# fhd-gs.net
KiCad netlist of a schematic drawn in EAGLE
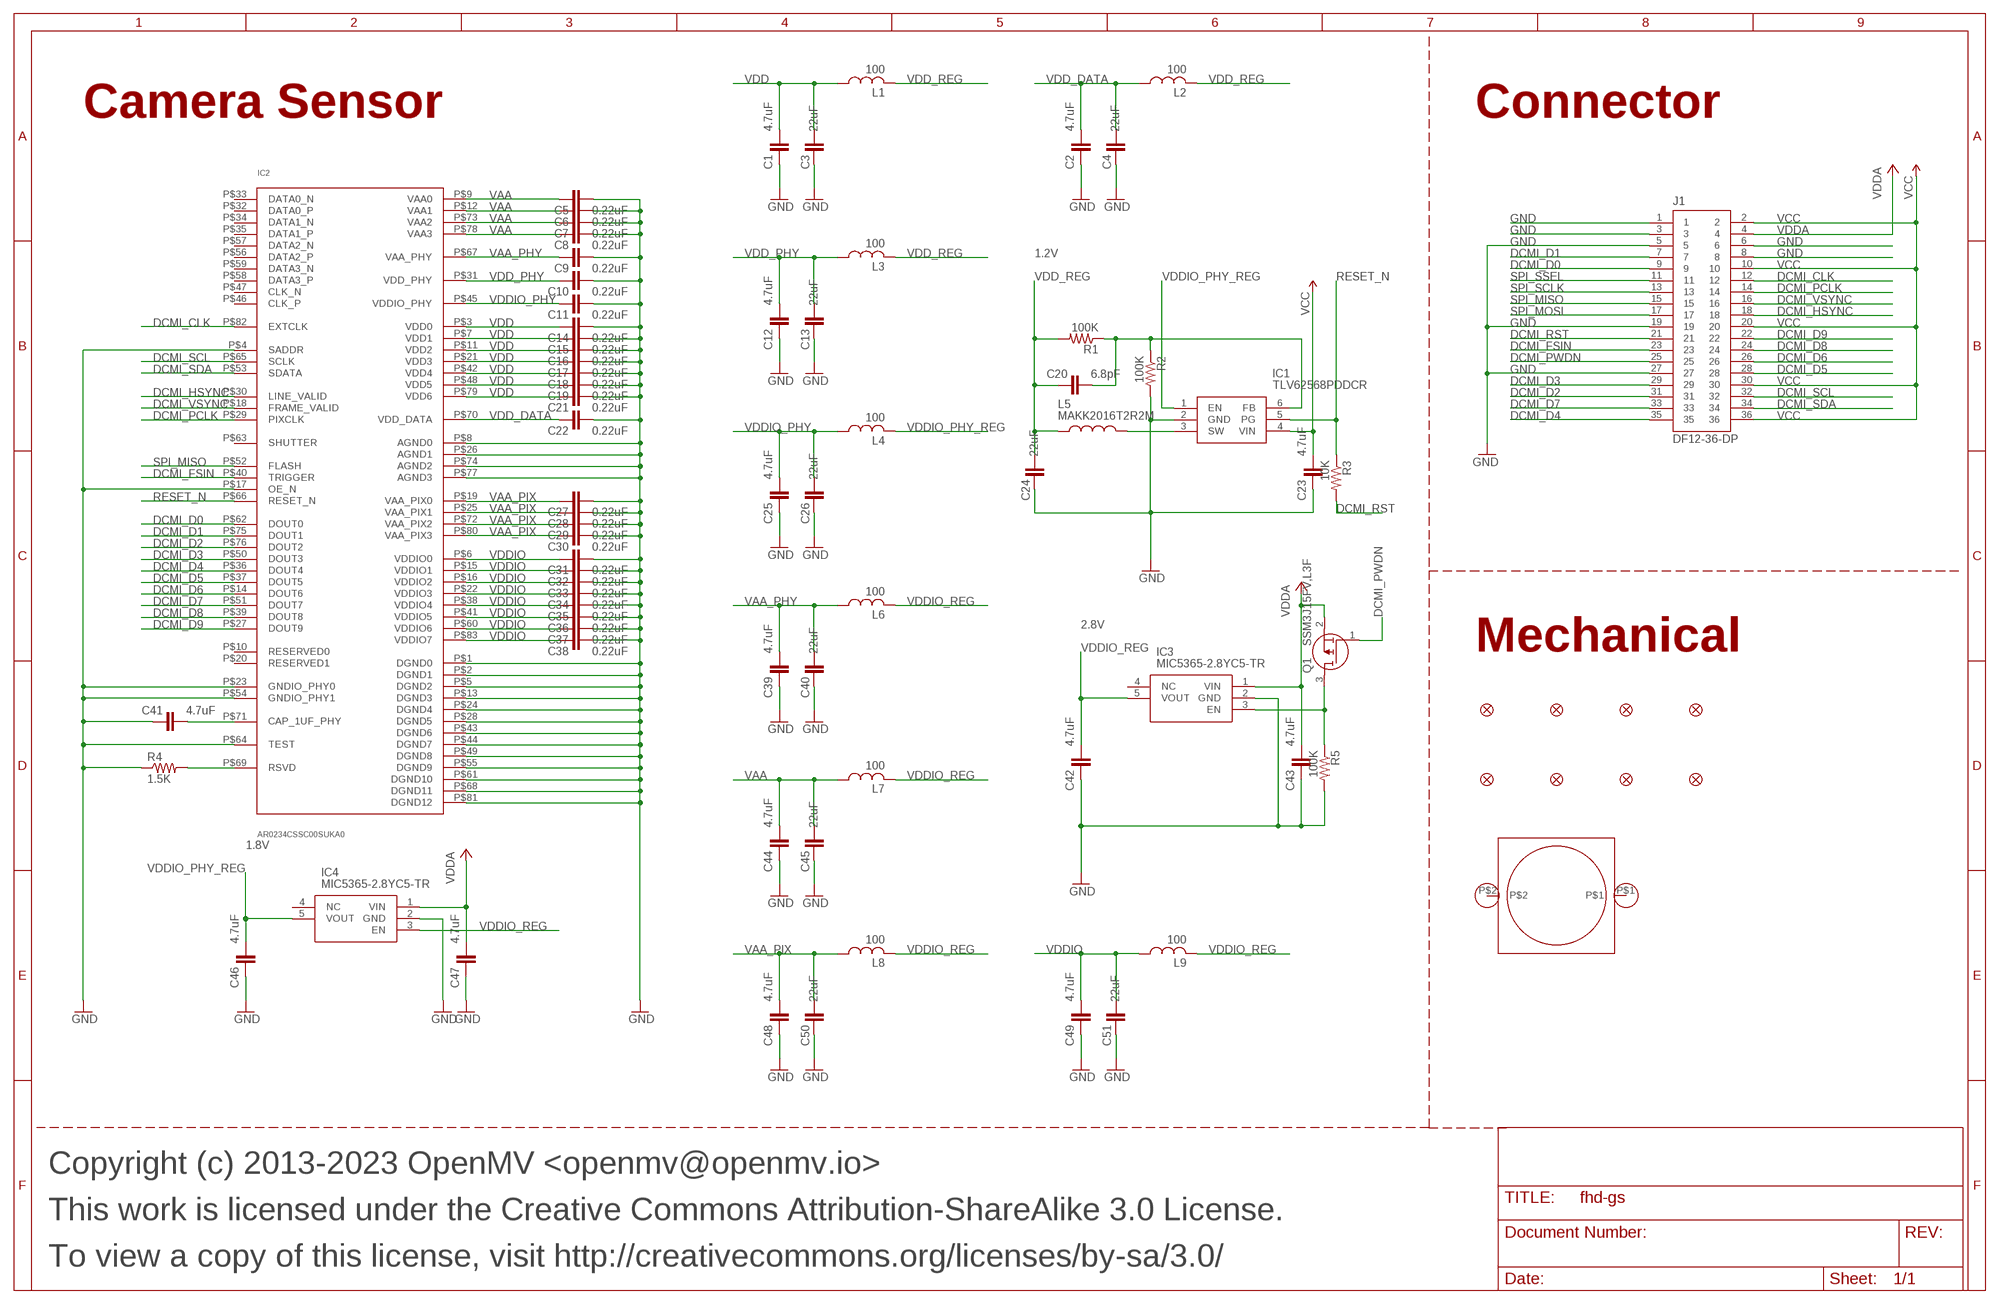
[diagram p0: schematic, sheet 1]

(export (version "E")
  (design (tool "Eeschema 10.0.6"))
  (components
    (comp (ref "C1")
      (value "4.7uF")
      (footprint "eagle-import:0402")
      (fields (field (name "MPN") "JMK105BBJ475MV-F"))
      (libsource (lib "eagle-import") (part "CAP_0402"))
    )
    (comp (ref "C2")
      (value "4.7uF")
      (footprint "eagle-import:0402")
      (fields (field (name "MPN") "JMK105BBJ475MV-F"))
      (libsource (lib "eagle-import") (part "CAP_0402"))
    )
    (comp (ref "C3")
      (value "22uF")
      (footprint "eagle-import:0805")
      (fields (field (name "MPN") "CL21A226MQQNNNE"))
      (libsource (lib "eagle-import") (part "22UF-0805-6.3V-20%"))
    )
    (comp (ref "C4")
      (value "22uF")
      (footprint "eagle-import:0805")
      (fields (field (name "MPN") "CL21A226MQQNNNE"))
      (libsource (lib "eagle-import") (part "22UF-0805-6.3V-20%"))
    )
    (comp (ref "C5")
      (value "0.22uF")
      (footprint "eagle-import:C0201")
      (fields (field (name "MPN") "GRM033R60J224ME15D"))
      (libsource (lib "eagle-import") (part "C-EUC0201"))
    )
    (comp (ref "C6")
      (value "0.22uF")
      (footprint "eagle-import:C0201")
      (fields (field (name "MPN") "GRM033R60J224ME15D"))
      (libsource (lib "eagle-import") (part "C-EUC0201"))
    )
    (comp (ref "C7")
      (value "0.22uF")
      (footprint "eagle-import:C0201")
      (fields (field (name "MPN") "GRM033R60J224ME15D"))
      (libsource (lib "eagle-import") (part "C-EUC0201"))
    )
    (comp (ref "C8")
      (value "0.22uF")
      (footprint "eagle-import:C0201")
      (fields (field (name "MPN") "GRM033R60J224ME15D"))
      (libsource (lib "eagle-import") (part "C-EUC0201"))
    )
    (comp (ref "C9")
      (value "0.22uF")
      (footprint "eagle-import:C0201")
      (fields (field (name "MPN") "GRM033R60J224ME15D"))
      (libsource (lib "eagle-import") (part "C-EUC0201"))
    )
    (comp (ref "C10")
      (value "0.22uF")
      (footprint "eagle-import:C0201")
      (fields (field (name "MPN") "GRM033R60J224ME15D"))
      (libsource (lib "eagle-import") (part "C-EUC0201"))
    )
    (comp (ref "C11")
      (value "0.22uF")
      (footprint "eagle-import:C0201")
      (fields (field (name "MPN") "GRM033R60J224ME15D"))
      (libsource (lib "eagle-import") (part "C-EUC0201"))
    )
    (comp (ref "C12")
      (value "4.7uF")
      (footprint "eagle-import:0402")
      (fields (field (name "MPN") "JMK105BBJ475MV-F"))
      (libsource (lib "eagle-import") (part "CAP_0402"))
    )
    (comp (ref "C13")
      (value "22uF")
      (footprint "eagle-import:0805")
      (fields (field (name "MPN") "CL21A226MQQNNNE"))
      (libsource (lib "eagle-import") (part "22UF-0805-6.3V-20%"))
    )
    (comp (ref "C14")
      (value "0.22uF")
      (footprint "eagle-import:C0201")
      (fields (field (name "MPN") "GRM033R60J224ME15D"))
      (libsource (lib "eagle-import") (part "C-EUC0201"))
    )
    (comp (ref "C15")
      (value "0.22uF")
      (footprint "eagle-import:C0201")
      (fields (field (name "MPN") "GRM033R60J224ME15D"))
      (libsource (lib "eagle-import") (part "C-EUC0201"))
    )
    (comp (ref "C16")
      (value "0.22uF")
      (footprint "eagle-import:C0201")
      (fields (field (name "MPN") "GRM033R60J224ME15D"))
      (libsource (lib "eagle-import") (part "C-EUC0201"))
    )
    (comp (ref "C17")
      (value "0.22uF")
      (footprint "eagle-import:C0201")
      (fields (field (name "MPN") "GRM033R60J224ME15D"))
      (libsource (lib "eagle-import") (part "C-EUC0201"))
    )
    (comp (ref "C18")
      (value "0.22uF")
      (footprint "eagle-import:C0201")
      (fields (field (name "MPN") "GRM033R60J224ME15D"))
      (libsource (lib "eagle-import") (part "C-EUC0201"))
    )
    (comp (ref "C19")
      (value "0.22uF")
      (footprint "eagle-import:C0201")
      (fields (field (name "MPN") "GRM033R60J224ME15D"))
      (libsource (lib "eagle-import") (part "C-EUC0201"))
    )
    (comp (ref "C20")
      (value "6.8pF")
      (footprint "eagle-import:0402")
      (fields (field (name "MPN") "GRM1555C1H6R8DA01D"))
      (libsource (lib "eagle-import") (part "CAP_0402"))
    )
    (comp (ref "C21")
      (value "0.22uF")
      (footprint "eagle-import:C0201")
      (fields (field (name "MPN") "GRM033R60J224ME15D"))
      (libsource (lib "eagle-import") (part "C-EUC0201"))
    )
    (comp (ref "C22")
      (value "0.22uF")
      (footprint "eagle-import:C0201")
      (fields (field (name "MPN") "GRM033R60J224ME15D"))
      (libsource (lib "eagle-import") (part "C-EUC0201"))
    )
    (comp (ref "C23")
      (value "4.7uF")
      (footprint "eagle-import:0402")
      (fields (field (name "MPN") "JMK105BBJ475MV-F"))
      (libsource (lib "eagle-import") (part "CAP_0402"))
    )
    (comp (ref "C24")
      (value "22uF")
      (footprint "eagle-import:0805")
      (fields (field (name "MPN") "CL21A226MQQNNNE"))
      (libsource (lib "eagle-import") (part "22UF-0805-6.3V-20%"))
    )
    (comp (ref "C25")
      (value "4.7uF")
      (footprint "eagle-import:0402")
      (fields (field (name "MPN") "JMK105BBJ475MV-F"))
      (libsource (lib "eagle-import") (part "CAP_0402"))
    )
    (comp (ref "C26")
      (value "22uF")
      (footprint "eagle-import:0805")
      (fields (field (name "MPN") "CL21A226MQQNNNE"))
      (libsource (lib "eagle-import") (part "22UF-0805-6.3V-20%"))
    )
    (comp (ref "C27")
      (value "0.22uF")
      (footprint "eagle-import:C0201")
      (fields (field (name "MPN") "GRM033R60J224ME15D"))
      (libsource (lib "eagle-import") (part "C-EUC0201"))
    )
    (comp (ref "C28")
      (value "0.22uF")
      (footprint "eagle-import:C0201")
      (fields (field (name "MPN") "GRM033R60J224ME15D"))
      (libsource (lib "eagle-import") (part "C-EUC0201"))
    )
    (comp (ref "C29")
      (value "0.22uF")
      (footprint "eagle-import:C0201")
      (fields (field (name "MPN") "GRM033R60J224ME15D"))
      (libsource (lib "eagle-import") (part "C-EUC0201"))
    )
    (comp (ref "C30")
      (value "0.22uF")
      (footprint "eagle-import:C0201")
      (fields (field (name "MPN") "GRM033R60J224ME15D"))
      (libsource (lib "eagle-import") (part "C-EUC0201"))
    )
    (comp (ref "C31")
      (value "0.22uF")
      (footprint "eagle-import:C0201")
      (fields (field (name "MPN") "GRM033R60J224ME15D"))
      (libsource (lib "eagle-import") (part "C-EUC0201"))
    )
    (comp (ref "C32")
      (value "0.22uF")
      (footprint "eagle-import:C0201")
      (fields (field (name "MPN") "GRM033R60J224ME15D"))
      (libsource (lib "eagle-import") (part "C-EUC0201"))
    )
    (comp (ref "C33")
      (value "0.22uF")
      (footprint "eagle-import:C0201")
      (fields (field (name "MPN") "GRM033R60J224ME15D"))
      (libsource (lib "eagle-import") (part "C-EUC0201"))
    )
    (comp (ref "C34")
      (value "0.22uF")
      (footprint "eagle-import:C0201")
      (fields (field (name "MPN") "GRM033R60J224ME15D"))
      (libsource (lib "eagle-import") (part "C-EUC0201"))
    )
    (comp (ref "C35")
      (value "0.22uF")
      (footprint "eagle-import:C0201")
      (fields (field (name "MPN") "GRM033R60J224ME15D"))
      (libsource (lib "eagle-import") (part "C-EUC0201"))
    )
    (comp (ref "C36")
      (value "0.22uF")
      (footprint "eagle-import:C0201")
      (fields (field (name "MPN") "GRM033R60J224ME15D"))
      (libsource (lib "eagle-import") (part "C-EUC0201"))
    )
    (comp (ref "C37")
      (value "0.22uF")
      (footprint "eagle-import:C0201")
      (fields (field (name "MPN") "GRM033R60J224ME15D"))
      (libsource (lib "eagle-import") (part "C-EUC0201"))
    )
    (comp (ref "C38")
      (value "0.22uF")
      (footprint "eagle-import:C0201")
      (fields (field (name "MPN") "GRM033R60J224ME15D"))
      (libsource (lib "eagle-import") (part "C-EUC0201"))
    )
    (comp (ref "C39")
      (value "4.7uF")
      (footprint "eagle-import:0402")
      (fields (field (name "MPN") "JMK105BBJ475MV-F"))
      (libsource (lib "eagle-import") (part "CAP_0402"))
    )
    (comp (ref "C40")
      (value "22uF")
      (footprint "eagle-import:0805")
      (fields (field (name "MPN") "CL21A226MQQNNNE"))
      (libsource (lib "eagle-import") (part "22UF-0805-6.3V-20%"))
    )
    (comp (ref "C41")
      (value "4.7uF")
      (footprint "eagle-import:0402")
      (fields (field (name "MPN") "JMK105BBJ475MV-F"))
      (libsource (lib "eagle-import") (part "CAP_0402"))
    )
    (comp (ref "C42")
      (value "4.7uF")
      (footprint "eagle-import:0402")
      (fields (field (name "MPN") "JMK105BBJ475MV-F"))
      (libsource (lib "eagle-import") (part "CAP_0402"))
    )
    (comp (ref "C43")
      (value "4.7uF")
      (footprint "eagle-import:0402")
      (fields (field (name "MPN") "JMK105BBJ475MV-F"))
      (libsource (lib "eagle-import") (part "CAP_0402"))
    )
    (comp (ref "C44")
      (value "4.7uF")
      (footprint "eagle-import:0402")
      (fields (field (name "MPN") "JMK105BBJ475MV-F"))
      (libsource (lib "eagle-import") (part "CAP_0402"))
    )
    (comp (ref "C45")
      (value "22uF")
      (footprint "eagle-import:0805")
      (fields (field (name "MPN") "CL21A226MQQNNNE"))
      (libsource (lib "eagle-import") (part "22UF-0805-6.3V-20%"))
    )
    (comp (ref "C46")
      (value "4.7uF")
      (footprint "eagle-import:0402")
      (fields (field (name "MPN") "JMK105BBJ475MV-F"))
      (libsource (lib "eagle-import") (part "CAP_0402"))
    )
    (comp (ref "C47")
      (value "4.7uF")
      (footprint "eagle-import:0402")
      (fields (field (name "MPN") "JMK105BBJ475MV-F"))
      (libsource (lib "eagle-import") (part "CAP_0402"))
    )
    (comp (ref "C48")
      (value "4.7uF")
      (footprint "eagle-import:0402")
      (fields (field (name "MPN") "JMK105BBJ475MV-F"))
      (libsource (lib "eagle-import") (part "CAP_0402"))
    )
    (comp (ref "C49")
      (value "4.7uF")
      (footprint "eagle-import:0402")
      (fields (field (name "MPN") "JMK105BBJ475MV-F"))
      (libsource (lib "eagle-import") (part "CAP_0402"))
    )
    (comp (ref "C50")
      (value "22uF")
      (footprint "eagle-import:0805")
      (fields (field (name "MPN") "CL21A226MQQNNNE"))
      (libsource (lib "eagle-import") (part "22UF-0805-6.3V-20%"))
    )
    (comp (ref "C51")
      (value "22uF")
      (footprint "eagle-import:0805")
      (fields (field (name "MPN") "CL21A226MQQNNNE"))
      (libsource (lib "eagle-import") (part "22UF-0805-6.3V-20%"))
    )
    (comp (ref "FD1")
      (value "FIDUCIAL1X2")
      (footprint "eagle-import:FIDUCIAL-1X2")
      (libsource (lib "eagle-import") (part "FIDUCIAL1X2"))
    )
    (comp (ref "FD2")
      (value "FIDUCIAL1X2")
      (footprint "eagle-import:FIDUCIAL-1X2")
      (libsource (lib "eagle-import") (part "FIDUCIAL1X2"))
    )
    (comp (ref "FD3")
      (value "FIDUCIAL1X2")
      (footprint "eagle-import:FIDUCIAL-1X2")
      (libsource (lib "eagle-import") (part "FIDUCIAL1X2"))
    )
    (comp (ref "FD4")
      (value "FIDUCIAL1X2")
      (footprint "eagle-import:FIDUCIAL-1X2")
      (libsource (lib "eagle-import") (part "FIDUCIAL1X2"))
    )
    (comp (ref "FD5")
      (value "FIDUCIAL1X2")
      (footprint "eagle-import:FIDUCIAL-1X2")
      (libsource (lib "eagle-import") (part "FIDUCIAL1X2"))
    )
    (comp (ref "FD6")
      (value "FIDUCIAL1X2")
      (footprint "eagle-import:FIDUCIAL-1X2")
      (libsource (lib "eagle-import") (part "FIDUCIAL1X2"))
    )
    (comp (ref "FD7")
      (value "FIDUCIAL1X2")
      (footprint "eagle-import:FIDUCIAL-1X2")
      (libsource (lib "eagle-import") (part "FIDUCIAL1X2"))
    )
    (comp (ref "FD8")
      (value "FIDUCIAL1X2")
      (footprint "eagle-import:FIDUCIAL-1X2")
      (libsource (lib "eagle-import") (part "FIDUCIAL1X2"))
    )
    (comp (ref "H1")
      (value "LENSMOUNT20MM")
      (footprint "eagle-import:LENSMOUNT-20MM")
      (libsource (lib "eagle-import") (part "LENSMOUNT20MM"))
    )
    (comp (ref "IC1")
      (value "TLV62568PDDCR")
      (footprint "eagle-import:SOT95P280X110-6N")
      (fields (field (name "MOUSER_PART_NUMBER") "595-TLV62568PDDCR"))
      (libsource (lib "eagle-import") (part "TLV62568PDDCR"))
    )
    (comp (ref "IC2")
      (value "AR0234CSSC00SUKA0")
      (footprint "eagle-import:AR0234CSSC00SUKA0")
      (libsource (lib "eagle-import") (part "AR0234CSSC00SUKA0"))
    )
    (comp (ref "IC3")
      (value "MIC5365-2.8YC5-TR")
      (footprint "eagle-import:SOT65P210X110-5N")
      (fields (field (name "MOUSER_PART_NUMBER") "998-MIC5365-2.8YC5TR"))
      (libsource (lib "eagle-import") (part "MIC5365-2.8YC5-TR"))
    )
    (comp (ref "IC4")
      (value "MIC5365-2.8YC5-TR")
      (footprint "eagle-import:SOT65P210X110-5N")
      (fields (field (name "MOUSER_PART_NUMBER") "998-MIC5365-2.8YC5TR"))
      (libsource (lib "eagle-import") (part "MIC5365-2.8YC5-TR"))
    )
    (comp (ref "J1")
      (value "DF12-36-DP")
      (footprint "eagle-import:DF12-36-DP")
      (fields (field (name "MPN") "DF12NB(3.0)-36DP-0.5V(51)"))
      (libsource (lib "eagle-import") (part "DF12-36-DP"))
    )
    (comp (ref "L1")
      (value "100")
      (footprint "eagle-import:0402")
      (fields (field (name "MPN") "MFBM1V1005-101-R"))
      (libsource (lib "eagle-import") (part "INDUCTOR_0402"))
    )
    (comp (ref "L2")
      (value "100")
      (footprint "eagle-import:0402")
      (fields (field (name "MPN") "MFBM1V1005-101-R"))
      (libsource (lib "eagle-import") (part "INDUCTOR_0402"))
    )
    (comp (ref "L3")
      (value "100")
      (footprint "eagle-import:0402")
      (fields (field (name "MPN") "MFBM1V1005-101-R"))
      (libsource (lib "eagle-import") (part "INDUCTOR_0402"))
    )
    (comp (ref "L4")
      (value "100")
      (footprint "eagle-import:0402")
      (fields (field (name "MPN") "MFBM1V1005-101-R"))
      (libsource (lib "eagle-import") (part "INDUCTOR_0402"))
    )
    (comp (ref "L5")
      (value "MAKK2016T2R2M")
      (footprint "eagle-import:INDC2016X100N")
      (fields (field (name "MF") "Taiyo Yuden"))
      (libsource (lib "eagle-import") (part "MAKK2016T2R2M"))
    )
    (comp (ref "L6")
      (value "100")
      (footprint "eagle-import:0402")
      (fields (field (name "MPN") "MFBM1V1005-101-R"))
      (libsource (lib "eagle-import") (part "INDUCTOR_0402"))
    )
    (comp (ref "L7")
      (value "100")
      (footprint "eagle-import:0402")
      (fields (field (name "MPN") "MFBM1V1005-101-R"))
      (libsource (lib "eagle-import") (part "INDUCTOR_0402"))
    )
    (comp (ref "L8")
      (value "100")
      (footprint "eagle-import:0402")
      (fields (field (name "MPN") "MFBM1V1005-101-R"))
      (libsource (lib "eagle-import") (part "INDUCTOR_0402"))
    )
    (comp (ref "L9")
      (value "100")
      (footprint "eagle-import:0402")
      (fields (field (name "MPN") "MFBM1V1005-101-R"))
      (libsource (lib "eagle-import") (part "INDUCTOR_0402"))
    )
    (comp (ref "Q1")
      (value "SSM3J15FV,L3F")
      (footprint "eagle-import:SSM3J15FVL3F")
      (fields (field (name "MOUSER_PART_NUMBER") "757-SSM3J15FVL3F"))
      (libsource (lib "eagle-import") (part "SSM3J15FV,L3F"))
    )
    (comp (ref "R1")
      (value "100K")
      (footprint "eagle-import:R0402")
      (fields (field (name "MPN") "AC0402FR-07100KL"))
      (libsource (lib "eagle-import") (part "R-US_R0402"))
    )
    (comp (ref "R2")
      (value "100K")
      (footprint "eagle-import:R0402")
      (fields (field (name "MPN") "AC0402FR-07100KL"))
      (libsource (lib "eagle-import") (part "R-US_R0402"))
    )
    (comp (ref "R3")
      (value "10K")
      (footprint "eagle-import:R0402")
      (fields (field (name "MPN") "AC0402FR-1310KL"))
      (libsource (lib "eagle-import") (part "R-US_R0402"))
    )
    (comp (ref "R4")
      (value "1.5K")
      (footprint "eagle-import:R0402")
      (fields (field (name "MPN") "RC0402FR-131K5L"))
      (libsource (lib "eagle-import") (part "R-US_R0402"))
    )
    (comp (ref "R5")
      (value "100K")
      (footprint "eagle-import:R0402")
      (fields (field (name "MPN") "AC0402FR-07100KL"))
      (libsource (lib "eagle-import") (part "R-US_R0402"))
    )
  )
  (nets
    (net (code "1") (name "/DCMI_CLK") (class "Default")
      (node (ref "IC2") (pin "P$82") (pinfunction "EXTCLK_P$82") (pintype "bidirectional"))
      (node (ref "J1") (pin "12") (pinfunction "12_12") (pintype "bidirectional"))
    )
    (net (code "2") (name "/DCMI_D0") (class "Default")
      (node (ref "IC2") (pin "P$62") (pinfunction "DOUT0_P$62") (pintype "bidirectional"))
      (node (ref "J1") (pin "9") (pinfunction "9_9") (pintype "bidirectional"))
    )
    (net (code "3") (name "/DCMI_D1") (class "Default")
      (node (ref "IC2") (pin "P$75") (pinfunction "DOUT1_P$75") (pintype "bidirectional"))
      (node (ref "J1") (pin "7") (pinfunction "7_7") (pintype "bidirectional"))
    )
    (net (code "4") (name "/DCMI_D2") (class "Default")
      (node (ref "IC2") (pin "P$76") (pinfunction "DOUT2_P$76") (pintype "bidirectional"))
      (node (ref "J1") (pin "31") (pinfunction "31_31") (pintype "bidirectional"))
    )
    (net (code "5") (name "/DCMI_D3") (class "Default")
      (node (ref "IC2") (pin "P$50") (pinfunction "DOUT3_P$50") (pintype "bidirectional"))
      (node (ref "J1") (pin "29") (pinfunction "29_29") (pintype "bidirectional"))
    )
    (net (code "6") (name "/DCMI_D4") (class "Default")
      (node (ref "IC2") (pin "P$36") (pinfunction "DOUT4_P$36") (pintype "bidirectional"))
      (node (ref "J1") (pin "35") (pinfunction "35_35") (pintype "bidirectional"))
    )
    (net (code "7") (name "/DCMI_D5") (class "Default")
      (node (ref "IC2") (pin "P$37") (pinfunction "DOUT5_P$37") (pintype "bidirectional"))
      (node (ref "J1") (pin "28") (pinfunction "28_28") (pintype "bidirectional"))
    )
    (net (code "8") (name "/DCMI_D6") (class "Default")
      (node (ref "IC2") (pin "P$14") (pinfunction "DOUT6_P$14") (pintype "bidirectional"))
      (node (ref "J1") (pin "26") (pinfunction "26_26") (pintype "bidirectional"))
    )
    (net (code "9") (name "/DCMI_D7") (class "Default")
      (node (ref "IC2") (pin "P$51") (pinfunction "DOUT7_P$51") (pintype "bidirectional"))
      (node (ref "J1") (pin "33") (pinfunction "33_33") (pintype "bidirectional"))
    )
    (net (code "10") (name "/DCMI_D8") (class "Default")
      (node (ref "IC2") (pin "P$39") (pinfunction "DOUT8_P$39") (pintype "bidirectional"))
      (node (ref "J1") (pin "24") (pinfunction "24_24") (pintype "bidirectional"))
    )
    (net (code "11") (name "/DCMI_D9") (class "Default")
      (node (ref "IC2") (pin "P$27") (pinfunction "DOUT9_P$27") (pintype "bidirectional"))
      (node (ref "J1") (pin "22") (pinfunction "22_22") (pintype "bidirectional"))
    )
    (net (code "12") (name "/DCMI_FSIN") (class "Default")
      (node (ref "IC2") (pin "P$40") (pinfunction "TRIGGER_P$40") (pintype "bidirectional"))
      (node (ref "J1") (pin "23") (pinfunction "23_23") (pintype "bidirectional"))
    )
    (net (code "13") (name "/DCMI_HSYNC") (class "Default")
      (node (ref "IC2") (pin "P$30") (pinfunction "LINE_VALID_P$30") (pintype "bidirectional"))
      (node (ref "J1") (pin "18") (pinfunction "18_18") (pintype "bidirectional"))
    )
    (net (code "14") (name "/DCMI_PCLK") (class "Default")
      (node (ref "IC2") (pin "P$29") (pinfunction "PIXCLK_P$29") (pintype "bidirectional"))
      (node (ref "J1") (pin "14") (pinfunction "14_14") (pintype "bidirectional"))
    )
    (net (code "15") (name "/DCMI_PWDN") (class "Default")
      (node (ref "J1") (pin "25") (pinfunction "25_25") (pintype "bidirectional"))
      (node (ref "Q1") (pin "1") (pinfunction "G_1") (pintype "bidirectional"))
    )
    (net (code "16") (name "/DCMI_RST") (class "Default")
      (node (ref "J1") (pin "21") (pinfunction "21_21") (pintype "bidirectional"))
      (node (ref "R3") (pin "2") (pinfunction "2_2") (pintype "passive"))
    )
    (net (code "17") (name "/DCMI_SCL") (class "Default")
      (node (ref "IC2") (pin "P$65") (pinfunction "SCLK_P$65") (pintype "bidirectional"))
      (node (ref "J1") (pin "32") (pinfunction "32_32") (pintype "bidirectional"))
    )
    (net (code "18") (name "/DCMI_SDA") (class "Default")
      (node (ref "IC2") (pin "P$53") (pinfunction "SDATA_P$53") (pintype "bidirectional"))
      (node (ref "J1") (pin "34") (pinfunction "34_34") (pintype "bidirectional"))
    )
    (net (code "19") (name "/DCMI_VSYNC") (class "Default")
      (node (ref "IC2") (pin "P$18") (pinfunction "FRAME_VALID_P$18") (pintype "bidirectional"))
      (node (ref "J1") (pin "16") (pinfunction "16_16") (pintype "bidirectional"))
    )
    (net (code "20") (name "/P$1") (class "Default")
      (node (ref "H1") (pin "P$1") (pinfunction "P$1_P$1") (pintype "power_in"))
    )
    (net (code "21") (name "/P$2") (class "Default")
      (node (ref "H1") (pin "P$2") (pinfunction "P$2_P$2") (pintype "power_in"))
    )
    (net (code "22") (name "/RESET_N") (class "Default")
      (node (ref "IC1") (pin "5") (pinfunction "PG_5") (pintype "bidirectional"))
      (node (ref "IC2") (pin "P$66") (pinfunction "RESET_N_P$66") (pintype "bidirectional"))
      (node (ref "R3") (pin "1") (pinfunction "1_1") (pintype "passive"))
    )
    (net (code "23") (name "/SPI_MISO") (class "Default")
      (node (ref "IC2") (pin "P$52") (pinfunction "FLASH_P$52") (pintype "bidirectional"))
      (node (ref "J1") (pin "15") (pinfunction "15_15") (pintype "bidirectional"))
    )
    (net (code "24") (name "/SPI_MOSI") (class "Default")
      (node (ref "J1") (pin "17") (pinfunction "17_17") (pintype "bidirectional"))
    )
    (net (code "25") (name "/SPI_SCLK") (class "Default")
      (node (ref "J1") (pin "13") (pinfunction "13_13") (pintype "bidirectional"))
    )
    (net (code "26") (name "/SPI_SSEL") (class "Default")
      (node (ref "J1") (pin "11") (pinfunction "11_11") (pintype "bidirectional"))
    )
    (net (code "27") (name "/VAA") (class "Default")
      (node (ref "C44") (pin "2") (pinfunction "2_2") (pintype "passive"))
      (node (ref "C45") (pin "2") (pinfunction "2_2") (pintype "passive"))
      (node (ref "C5") (pin "1") (pinfunction "1_1") (pintype "passive"))
      (node (ref "C6") (pin "1") (pinfunction "1_1") (pintype "passive"))
      (node (ref "C7") (pin "1") (pinfunction "1_1") (pintype "passive"))
      (node (ref "C8") (pin "1") (pinfunction "1_1") (pintype "passive"))
      (node (ref "IC2") (pin "P$12") (pinfunction "VAA1_P$12") (pintype "bidirectional"))
      (node (ref "IC2") (pin "P$73") (pinfunction "VAA2_P$73") (pintype "bidirectional"))
      (node (ref "IC2") (pin "P$78") (pinfunction "VAA3_P$78") (pintype "bidirectional"))
      (node (ref "IC2") (pin "P$9") (pinfunction "VAA0_P$9") (pintype "bidirectional"))
      (node (ref "L7") (pin "1") (pinfunction "P$1_1") (pintype "passive"))
    )
    (net (code "28") (name "/VAA_PHY") (class "Default")
      (node (ref "C39") (pin "2") (pinfunction "2_2") (pintype "passive"))
      (node (ref "C40") (pin "2") (pinfunction "2_2") (pintype "passive"))
      (node (ref "C9") (pin "1") (pinfunction "1_1") (pintype "passive"))
      (node (ref "IC2") (pin "P$67") (pinfunction "VAA_PHY_P$67") (pintype "bidirectional"))
      (node (ref "L6") (pin "1") (pinfunction "P$1_1") (pintype "passive"))
    )
    (net (code "29") (name "/VAA_PIX") (class "Default")
      (node (ref "C27") (pin "1") (pinfunction "1_1") (pintype "passive"))
      (node (ref "C28") (pin "1") (pinfunction "1_1") (pintype "passive"))
      (node (ref "C29") (pin "1") (pinfunction "1_1") (pintype "passive"))
      (node (ref "C30") (pin "1") (pinfunction "1_1") (pintype "passive"))
      (node (ref "C48") (pin "2") (pinfunction "2_2") (pintype "passive"))
      (node (ref "C50") (pin "2") (pinfunction "2_2") (pintype "passive"))
      (node (ref "IC2") (pin "P$19") (pinfunction "VAA_PIX0_P$19") (pintype "bidirectional"))
      (node (ref "IC2") (pin "P$25") (pinfunction "VAA_PIX1_P$25") (pintype "bidirectional"))
      (node (ref "IC2") (pin "P$72") (pinfunction "VAA_PIX2_P$72") (pintype "bidirectional"))
      (node (ref "IC2") (pin "P$80") (pinfunction "VAA_PIX3_P$80") (pintype "bidirectional"))
      (node (ref "L8") (pin "1") (pinfunction "P$1_1") (pintype "passive"))
    )
    (net (code "30") (name "/VDD") (class "Default")
      (node (ref "C1") (pin "2") (pinfunction "2_2") (pintype "passive"))
      (node (ref "C14") (pin "1") (pinfunction "1_1") (pintype "passive"))
      (node (ref "C15") (pin "1") (pinfunction "1_1") (pintype "passive"))
      (node (ref "C16") (pin "1") (pinfunction "1_1") (pintype "passive"))
      (node (ref "C17") (pin "1") (pinfunction "1_1") (pintype "passive"))
      (node (ref "C18") (pin "1") (pinfunction "1_1") (pintype "passive"))
      (node (ref "C19") (pin "1") (pinfunction "1_1") (pintype "passive"))
      (node (ref "C21") (pin "1") (pinfunction "1_1") (pintype "passive"))
      (node (ref "C3") (pin "2") (pinfunction "2_2") (pintype "passive"))
      (node (ref "IC2") (pin "P$11") (pinfunction "VDD2_P$11") (pintype "bidirectional"))
      (node (ref "IC2") (pin "P$21") (pinfunction "VDD3_P$21") (pintype "bidirectional"))
      (node (ref "IC2") (pin "P$3") (pinfunction "VDD0_P$3") (pintype "bidirectional"))
      (node (ref "IC2") (pin "P$42") (pinfunction "VDD4_P$42") (pintype "bidirectional"))
      (node (ref "IC2") (pin "P$48") (pinfunction "VDD5_P$48") (pintype "bidirectional"))
      (node (ref "IC2") (pin "P$7") (pinfunction "VDD1_P$7") (pintype "bidirectional"))
      (node (ref "IC2") (pin "P$79") (pinfunction "VDD6_P$79") (pintype "bidirectional"))
      (node (ref "L1") (pin "1") (pinfunction "P$1_1") (pintype "passive"))
    )
    (net (code "31") (name "/VDDIO") (class "Default")
      (node (ref "C31") (pin "1") (pinfunction "1_1") (pintype "passive"))
      (node (ref "C32") (pin "1") (pinfunction "1_1") (pintype "passive"))
      (node (ref "C33") (pin "1") (pinfunction "1_1") (pintype "passive"))
      (node (ref "C34") (pin "1") (pinfunction "1_1") (pintype "passive"))
      (node (ref "C35") (pin "1") (pinfunction "1_1") (pintype "passive"))
      (node (ref "C36") (pin "1") (pinfunction "1_1") (pintype "passive"))
      (node (ref "C37") (pin "1") (pinfunction "1_1") (pintype "passive"))
      (node (ref "C38") (pin "1") (pinfunction "1_1") (pintype "passive"))
      (node (ref "C49") (pin "2") (pinfunction "2_2") (pintype "passive"))
      (node (ref "C51") (pin "2") (pinfunction "2_2") (pintype "passive"))
      (node (ref "IC2") (pin "P$15") (pinfunction "VDDIO1_P$15") (pintype "bidirectional"))
      (node (ref "IC2") (pin "P$16") (pinfunction "VDDIO2_P$16") (pintype "bidirectional"))
      (node (ref "IC2") (pin "P$22") (pinfunction "VDDIO3_P$22") (pintype "bidirectional"))
      (node (ref "IC2") (pin "P$38") (pinfunction "VDDIO4_P$38") (pintype "bidirectional"))
      (node (ref "IC2") (pin "P$41") (pinfunction "VDDIO5_P$41") (pintype "bidirectional"))
      (node (ref "IC2") (pin "P$6") (pinfunction "VDDIO0_P$6") (pintype "bidirectional"))
      (node (ref "IC2") (pin "P$60") (pinfunction "VDDIO6_P$60") (pintype "bidirectional"))
      (node (ref "IC2") (pin "P$83") (pinfunction "VDDIO7_P$83") (pintype "bidirectional"))
      (node (ref "L9") (pin "1") (pinfunction "P$1_1") (pintype "passive"))
    )
    (net (code "32") (name "/VDDIO_PHY") (class "Default")
      (node (ref "C11") (pin "1") (pinfunction "1_1") (pintype "passive"))
      (node (ref "C25") (pin "2") (pinfunction "2_2") (pintype "passive"))
      (node (ref "C26") (pin "2") (pinfunction "2_2") (pintype "passive"))
      (node (ref "IC2") (pin "P$45") (pinfunction "VDDIO_PHY_P$45") (pintype "bidirectional"))
      (node (ref "L4") (pin "1") (pinfunction "P$1_1") (pintype "passive"))
    )
    (net (code "33") (name "/VDDIO_PHY_REG") (class "Default")
      (node (ref "C46") (pin "2") (pinfunction "2_2") (pintype "passive"))
      (node (ref "IC1") (pin "1") (pinfunction "EN_1") (pintype "bidirectional"))
      (node (ref "IC4") (pin "5") (pinfunction "VOUT_5") (pintype "bidirectional"))
      (node (ref "L4") (pin "2") (pinfunction "P$2_2") (pintype "passive"))
    )
    (net (code "34") (name "/VDDIO_REG") (class "Default")
      (node (ref "C42") (pin "2") (pinfunction "2_2") (pintype "passive"))
      (node (ref "IC3") (pin "5") (pinfunction "VOUT_5") (pintype "bidirectional"))
      (node (ref "IC4") (pin "3") (pinfunction "EN_3") (pintype "bidirectional"))
      (node (ref "L6") (pin "2") (pinfunction "P$2_2") (pintype "passive"))
      (node (ref "L7") (pin "2") (pinfunction "P$2_2") (pintype "passive"))
      (node (ref "L8") (pin "2") (pinfunction "P$2_2") (pintype "passive"))
      (node (ref "L9") (pin "2") (pinfunction "P$2_2") (pintype "passive"))
    )
    (net (code "35") (name "/VDD_DATA") (class "Default")
      (node (ref "C2") (pin "2") (pinfunction "2_2") (pintype "passive"))
      (node (ref "C22") (pin "1") (pinfunction "1_1") (pintype "passive"))
      (node (ref "C4") (pin "2") (pinfunction "2_2") (pintype "passive"))
      (node (ref "IC2") (pin "P$70") (pinfunction "VDD_DATA_P$70") (pintype "bidirectional"))
      (node (ref "L2") (pin "1") (pinfunction "P$1_1") (pintype "passive"))
    )
    (net (code "36") (name "/VDD_PHY") (class "Default")
      (node (ref "C10") (pin "1") (pinfunction "1_1") (pintype "passive"))
      (node (ref "C12") (pin "2") (pinfunction "2_2") (pintype "passive"))
      (node (ref "C13") (pin "2") (pinfunction "2_2") (pintype "passive"))
      (node (ref "IC2") (pin "P$31") (pinfunction "VDD_PHY_P$31") (pintype "bidirectional"))
      (node (ref "L3") (pin "1") (pinfunction "P$1_1") (pintype "passive"))
    )
    (net (code "37") (name "/VDD_REG") (class "Default")
      (node (ref "C20") (pin "1") (pinfunction "1_1") (pintype "passive"))
      (node (ref "C24") (pin "2") (pinfunction "2_2") (pintype "passive"))
      (node (ref "L1") (pin "2") (pinfunction "P$2_2") (pintype "passive"))
      (node (ref "L2") (pin "2") (pinfunction "P$2_2") (pintype "passive"))
      (node (ref "L3") (pin "2") (pinfunction "P$2_2") (pintype "passive"))
      (node (ref "L5") (pin "1") (pinfunction "1_1") (pintype "passive"))
      (node (ref "R1") (pin "2") (pinfunction "2_2") (pintype "passive"))
    )
    (net (code "38") (name "GND") (class "Default")
      (node (ref "C1") (pin "1") (pinfunction "1_1") (pintype "passive"))
      (node (ref "C10") (pin "2") (pinfunction "2_2") (pintype "passive"))
      (node (ref "C11") (pin "2") (pinfunction "2_2") (pintype "passive"))
      (node (ref "C12") (pin "1") (pinfunction "1_1") (pintype "passive"))
      (node (ref "C13") (pin "1") (pinfunction "1_1") (pintype "passive"))
      (node (ref "C14") (pin "2") (pinfunction "2_2") (pintype "passive"))
      (node (ref "C15") (pin "2") (pinfunction "2_2") (pintype "passive"))
      (node (ref "C16") (pin "2") (pinfunction "2_2") (pintype "passive"))
      (node (ref "C17") (pin "2") (pinfunction "2_2") (pintype "passive"))
      (node (ref "C18") (pin "2") (pinfunction "2_2") (pintype "passive"))
      (node (ref "C19") (pin "2") (pinfunction "2_2") (pintype "passive"))
      (node (ref "C2") (pin "1") (pinfunction "1_1") (pintype "passive"))
      (node (ref "C21") (pin "2") (pinfunction "2_2") (pintype "passive"))
      (node (ref "C22") (pin "2") (pinfunction "2_2") (pintype "passive"))
      (node (ref "C23") (pin "1") (pinfunction "1_1") (pintype "passive"))
      (node (ref "C24") (pin "1") (pinfunction "1_1") (pintype "passive"))
      (node (ref "C25") (pin "1") (pinfunction "1_1") (pintype "passive"))
      (node (ref "C26") (pin "1") (pinfunction "1_1") (pintype "passive"))
      (node (ref "C27") (pin "2") (pinfunction "2_2") (pintype "passive"))
      (node (ref "C28") (pin "2") (pinfunction "2_2") (pintype "passive"))
      (node (ref "C29") (pin "2") (pinfunction "2_2") (pintype "passive"))
      (node (ref "C3") (pin "1") (pinfunction "1_1") (pintype "passive"))
      (node (ref "C30") (pin "2") (pinfunction "2_2") (pintype "passive"))
      (node (ref "C31") (pin "2") (pinfunction "2_2") (pintype "passive"))
      (node (ref "C32") (pin "2") (pinfunction "2_2") (pintype "passive"))
      (node (ref "C33") (pin "2") (pinfunction "2_2") (pintype "passive"))
      (node (ref "C34") (pin "2") (pinfunction "2_2") (pintype "passive"))
      (node (ref "C35") (pin "2") (pinfunction "2_2") (pintype "passive"))
      (node (ref "C36") (pin "2") (pinfunction "2_2") (pintype "passive"))
      (node (ref "C37") (pin "2") (pinfunction "2_2") (pintype "passive"))
      (node (ref "C38") (pin "2") (pinfunction "2_2") (pintype "passive"))
      (node (ref "C39") (pin "1") (pinfunction "1_1") (pintype "passive"))
      (node (ref "C4") (pin "1") (pinfunction "1_1") (pintype "passive"))
      (node (ref "C40") (pin "1") (pinfunction "1_1") (pintype "passive"))
      (node (ref "C41") (pin "1") (pinfunction "1_1") (pintype "passive"))
      (node (ref "C42") (pin "1") (pinfunction "1_1") (pintype "passive"))
      (node (ref "C43") (pin "1") (pinfunction "1_1") (pintype "passive"))
      (node (ref "C44") (pin "1") (pinfunction "1_1") (pintype "passive"))
      (node (ref "C45") (pin "1") (pinfunction "1_1") (pintype "passive"))
      (node (ref "C46") (pin "1") (pinfunction "1_1") (pintype "passive"))
      (node (ref "C47") (pin "1") (pinfunction "1_1") (pintype "passive"))
      (node (ref "C48") (pin "1") (pinfunction "1_1") (pintype "passive"))
      (node (ref "C49") (pin "1") (pinfunction "1_1") (pintype "passive"))
      (node (ref "C5") (pin "2") (pinfunction "2_2") (pintype "passive"))
      (node (ref "C50") (pin "1") (pinfunction "1_1") (pintype "passive"))
      (node (ref "C51") (pin "1") (pinfunction "1_1") (pintype "passive"))
      (node (ref "C6") (pin "2") (pinfunction "2_2") (pintype "passive"))
      (node (ref "C7") (pin "2") (pinfunction "2_2") (pintype "passive"))
      (node (ref "C8") (pin "2") (pinfunction "2_2") (pintype "passive"))
      (node (ref "C9") (pin "2") (pinfunction "2_2") (pintype "passive"))
      (node (ref "IC1") (pin "2") (pinfunction "GND_2") (pintype "bidirectional"))
      (node (ref "IC2") (pin "P$1") (pinfunction "DGND0_P$1") (pintype "bidirectional"))
      (node (ref "IC2") (pin "P$13") (pinfunction "DGND3_P$13") (pintype "bidirectional"))
      (node (ref "IC2") (pin "P$17") (pinfunction "OE_N_P$17") (pintype "bidirectional"))
      (node (ref "IC2") (pin "P$2") (pinfunction "DGND1_P$2") (pintype "bidirectional"))
      (node (ref "IC2") (pin "P$23") (pinfunction "GNDIO_PHY0_P$23") (pintype "bidirectional"))
      (node (ref "IC2") (pin "P$24") (pinfunction "DGND4_P$24") (pintype "bidirectional"))
      (node (ref "IC2") (pin "P$26") (pinfunction "AGND1_P$26") (pintype "bidirectional"))
      (node (ref "IC2") (pin "P$28") (pinfunction "DGND5_P$28") (pintype "bidirectional"))
      (node (ref "IC2") (pin "P$4") (pinfunction "SADDR_P$4") (pintype "bidirectional"))
      (node (ref "IC2") (pin "P$43") (pinfunction "DGND6_P$43") (pintype "bidirectional"))
      (node (ref "IC2") (pin "P$44") (pinfunction "DGND7_P$44") (pintype "bidirectional"))
      (node (ref "IC2") (pin "P$49") (pinfunction "DGND8_P$49") (pintype "bidirectional"))
      (node (ref "IC2") (pin "P$5") (pinfunction "DGND2_P$5") (pintype "bidirectional"))
      (node (ref "IC2") (pin "P$54") (pinfunction "GNDIO_PHY1_P$54") (pintype "bidirectional"))
      (node (ref "IC2") (pin "P$55") (pinfunction "DGND9_P$55") (pintype "bidirectional"))
      (node (ref "IC2") (pin "P$61") (pinfunction "DGND10_P$61") (pintype "bidirectional"))
      (node (ref "IC2") (pin "P$64") (pinfunction "TEST_P$64") (pintype "bidirectional"))
      (node (ref "IC2") (pin "P$68") (pinfunction "DGND11_P$68") (pintype "bidirectional"))
      (node (ref "IC2") (pin "P$74") (pinfunction "AGND2_P$74") (pintype "bidirectional"))
      (node (ref "IC2") (pin "P$77") (pinfunction "AGND3_P$77") (pintype "bidirectional"))
      (node (ref "IC2") (pin "P$8") (pinfunction "AGND0_P$8") (pintype "bidirectional"))
      (node (ref "IC2") (pin "P$81") (pinfunction "DGND12_P$81") (pintype "bidirectional"))
      (node (ref "IC3") (pin "2") (pinfunction "GND_2") (pintype "bidirectional"))
      (node (ref "IC4") (pin "2") (pinfunction "GND_2") (pintype "bidirectional"))
      (node (ref "J1") (pin "1") (pinfunction "1_1") (pintype "bidirectional"))
      (node (ref "J1") (pin "19") (pinfunction "19_19") (pintype "bidirectional"))
      (node (ref "J1") (pin "27") (pinfunction "27_27") (pintype "bidirectional"))
      (node (ref "J1") (pin "3") (pinfunction "3_3") (pintype "bidirectional"))
      (node (ref "J1") (pin "5") (pinfunction "5_5") (pintype "bidirectional"))
      (node (ref "J1") (pin "6") (pinfunction "6_6") (pintype "bidirectional"))
      (node (ref "J1") (pin "8") (pinfunction "8_8") (pintype "bidirectional"))
      (node (ref "R2") (pin "2") (pinfunction "2_2") (pintype "passive"))
      (node (ref "R4") (pin "1") (pinfunction "1_1") (pintype "passive"))
      (node (ref "R5") (pin "2") (pinfunction "2_2") (pintype "passive"))
    )
    (net (code "39") (name "Net-(IC1-FB)") (class "Default")
      (node (ref "C20") (pin "2") (pinfunction "2_2") (pintype "passive"))
      (node (ref "IC1") (pin "6") (pinfunction "FB_6") (pintype "bidirectional"))
      (node (ref "R1") (pin "1") (pinfunction "1_1") (pintype "passive"))
      (node (ref "R2") (pin "1") (pinfunction "1_1") (pintype "passive"))
    )
    (net (code "40") (name "Net-(IC1-SW)") (class "Default")
      (node (ref "IC1") (pin "3") (pinfunction "SW_3") (pintype "bidirectional"))
      (node (ref "L5") (pin "2") (pinfunction "2_2") (pintype "passive"))
    )
    (net (code "41") (name "Net-(IC2-CAP_1UF_PHY)") (class "Default")
      (node (ref "C41") (pin "2") (pinfunction "2_2") (pintype "passive"))
      (node (ref "IC2") (pin "P$71") (pinfunction "CAP_1UF_PHY_P$71") (pintype "bidirectional"))
    )
    (net (code "42") (name "Net-(IC2-RSVD)") (class "Default")
      (node (ref "IC2") (pin "P$69") (pinfunction "RSVD_P$69") (pintype "bidirectional"))
      (node (ref "R4") (pin "2") (pinfunction "2_2") (pintype "passive"))
    )
    (net (code "43") (name "Net-(IC3-EN)") (class "Default")
      (node (ref "IC3") (pin "3") (pinfunction "EN_3") (pintype "bidirectional"))
      (node (ref "Q1") (pin "3") (pinfunction "D_3") (pintype "bidirectional"))
      (node (ref "R5") (pin "1") (pinfunction "1_1") (pintype "passive"))
    )
    (net (code "44") (name "VCC") (class "Default")
      (node (ref "C23") (pin "2") (pinfunction "2_2") (pintype "passive"))
      (node (ref "IC1") (pin "4") (pinfunction "VIN_4") (pintype "bidirectional"))
      (node (ref "J1") (pin "10") (pinfunction "10_10") (pintype "bidirectional"))
      (node (ref "J1") (pin "2") (pinfunction "2_2") (pintype "bidirectional"))
      (node (ref "J1") (pin "20") (pinfunction "20_20") (pintype "bidirectional"))
      (node (ref "J1") (pin "30") (pinfunction "30_30") (pintype "bidirectional"))
      (node (ref "J1") (pin "36") (pinfunction "36_36") (pintype "bidirectional"))
    )
    (net (code "45") (name "VDDA") (class "Default")
      (node (ref "C43") (pin "2") (pinfunction "2_2") (pintype "passive"))
      (node (ref "C47") (pin "2") (pinfunction "2_2") (pintype "passive"))
      (node (ref "IC3") (pin "1") (pinfunction "VIN_1") (pintype "bidirectional"))
      (node (ref "IC4") (pin "1") (pinfunction "VIN_1") (pintype "bidirectional"))
      (node (ref "J1") (pin "4") (pinfunction "4_4") (pintype "bidirectional"))
      (node (ref "Q1") (pin "2") (pinfunction "S_2") (pintype "bidirectional"))
    )
    (net (code "46") (name "unconnected-(IC2-CLK_N-PadP$47)") (class "Default")
      (node (ref "IC2") (pin "P$47") (pinfunction "CLK_N_P$47") (pintype "bidirectional"))
    )
    (net (code "47") (name "unconnected-(IC2-CLK_P-PadP$46)") (class "Default")
      (node (ref "IC2") (pin "P$46") (pinfunction "CLK_P_P$46") (pintype "bidirectional"))
    )
    (net (code "48") (name "unconnected-(IC2-DATA0_N-PadP$33)") (class "Default")
      (node (ref "IC2") (pin "P$33") (pinfunction "DATA0_N_P$33") (pintype "bidirectional"))
    )
    (net (code "49") (name "unconnected-(IC2-DATA0_P-PadP$32)") (class "Default")
      (node (ref "IC2") (pin "P$32") (pinfunction "DATA0_P_P$32") (pintype "bidirectional"))
    )
    (net (code "50") (name "unconnected-(IC2-DATA1_N-PadP$34)") (class "Default")
      (node (ref "IC2") (pin "P$34") (pinfunction "DATA1_N_P$34") (pintype "bidirectional"))
    )
    (net (code "51") (name "unconnected-(IC2-DATA1_P-PadP$35)") (class "Default")
      (node (ref "IC2") (pin "P$35") (pinfunction "DATA1_P_P$35") (pintype "bidirectional"))
    )
    (net (code "52") (name "unconnected-(IC2-DATA2_N-PadP$57)") (class "Default")
      (node (ref "IC2") (pin "P$57") (pinfunction "DATA2_N_P$57") (pintype "bidirectional"))
    )
    (net (code "53") (name "unconnected-(IC2-DATA2_P-PadP$56)") (class "Default")
      (node (ref "IC2") (pin "P$56") (pinfunction "DATA2_P_P$56") (pintype "bidirectional"))
    )
    (net (code "54") (name "unconnected-(IC2-DATA3_N-PadP$59)") (class "Default")
      (node (ref "IC2") (pin "P$59") (pinfunction "DATA3_N_P$59") (pintype "bidirectional"))
    )
    (net (code "55") (name "unconnected-(IC2-DATA3_P-PadP$58)") (class "Default")
      (node (ref "IC2") (pin "P$58") (pinfunction "DATA3_P_P$58") (pintype "bidirectional"))
    )
    (net (code "56") (name "unconnected-(IC2-RESERVED0-PadP$10)") (class "Default")
      (node (ref "IC2") (pin "P$10") (pinfunction "RESERVED0_P$10") (pintype "bidirectional"))
    )
    (net (code "57") (name "unconnected-(IC2-RESERVED1-PadP$20)") (class "Default")
      (node (ref "IC2") (pin "P$20") (pinfunction "RESERVED1_P$20") (pintype "bidirectional"))
    )
    (net (code "58") (name "unconnected-(IC2-SHUTTER-PadP$63)") (class "Default")
      (node (ref "IC2") (pin "P$63") (pinfunction "SHUTTER_P$63") (pintype "bidirectional"))
    )
    (net (code "59") (name "unconnected-(IC3-NC-Pad4)") (class "Default")
      (node (ref "IC3") (pin "4") (pinfunction "NC_4") (pintype "no_connect"))
    )
    (net (code "60") (name "unconnected-(IC4-NC-Pad4)") (class "Default")
      (node (ref "IC4") (pin "4") (pinfunction "NC_4") (pintype "no_connect"))
    )
  )
)
